# ProPrj_CLOCK_2026-02-21.net
KiCad netlist of a schematic drawn in EasyEDA Pro
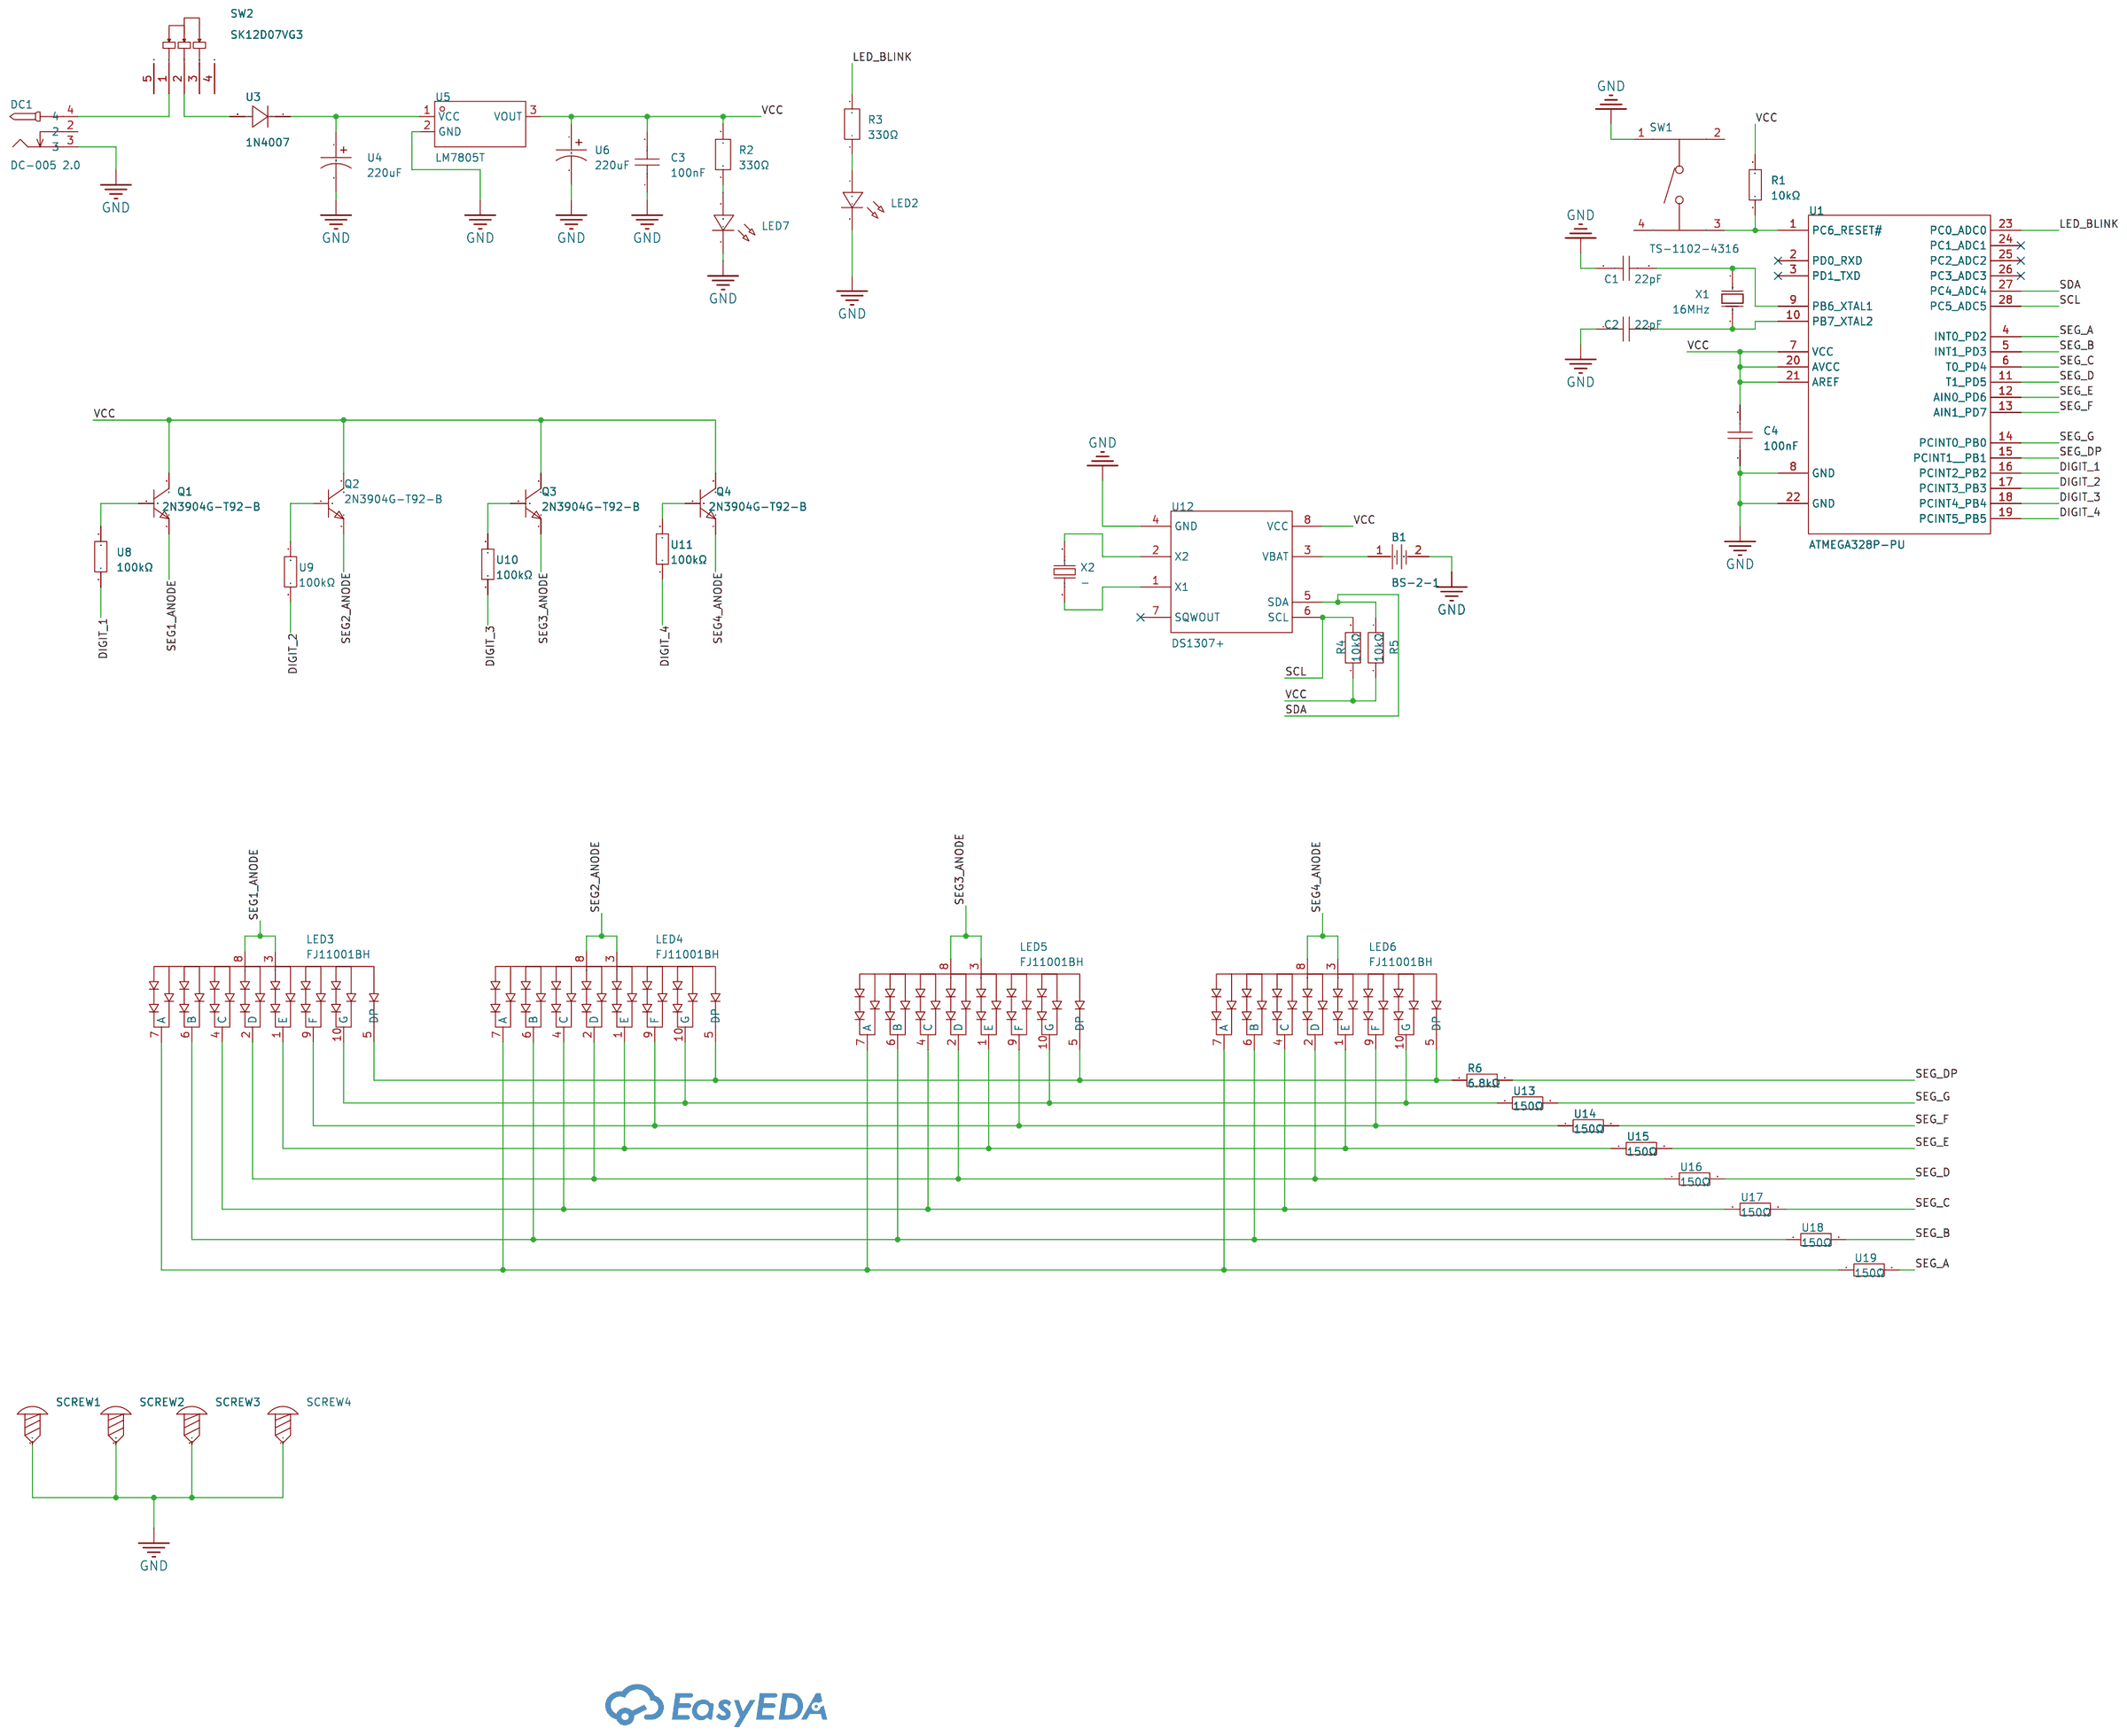
[diagram p0: schematic sheet]

(export (version "E")
  (design (tool "Eeschema 10.0.6"))
  (components
    (comp (ref "B1")
      (value "BS-2-1")
      (footprint "easyedapro:BAT-TH_BS-2-1")
      (fields (field (name "Manufacturer") "QIJEY"))
      (libsource (lib "easyedapro") (part "CR2032-BS-2-1"))
    )
    (comp (ref "C1")
      (value "22pF")
      (footprint "easyedapro:CAP-TH_L5.8-W2.4-P2.54-D0.6")
      (fields
        (field (name "Manufacturer Part") "CC1H220KA1EDCH4B1100")
        (field (name "Manufacturer") "Dersonic(德尔创)")
      )
      (libsource (lib "easyedapro") (part "CC1H220KA1EDCH4B1100"))
    )
    (comp (ref "C2")
      (value "22pF")
      (footprint "easyedapro:CAP-TH_L5.8-W2.4-P2.54-D0.6")
      (fields
        (field (name "Manufacturer Part") "CC1H220KA1EDCH4B1100")
        (field (name "Manufacturer") "Dersonic(德尔创)")
      )
      (libsource (lib "easyedapro") (part "CC1H220KA1EDCH4B1100"))
    )
    (comp (ref "C3")
      (value "100nF")
      (footprint "easyedapro:CAP-TH_L5.0-W2.5-P5.00-D1.0")
      (fields
        (field (name "Manufacturer Part") "CC1H104MC1FD3F6C10MF")
        (field (name "Manufacturer") "Dersonic(德尔创)")
      )
      (libsource (lib "easyedapro") (part "CC1H104MC1FD3F6C10MF"))
    )
    (comp (ref "C4")
      (value "100nF")
      (footprint "easyedapro:CAP-TH_L5.0-W2.5-P5.00-D1.0")
      (fields
        (field (name "Manufacturer Part") "CC1H104MC1FD3F6C10MF")
        (field (name "Manufacturer") "Dersonic(德尔创)")
      )
      (libsource (lib "easyedapro") (part "CC1H104MC1FD3F6C10MF"))
    )
    (comp (ref "DC1")
      (value "DC-005 2.0")
      (footprint "easyedapro:DC-IN-TH_DC-005-5.5-2.0")
      (fields (field (name "Manufacturer") "BOOMELE(博穆精密)"))
      (libsource (lib "easyedapro") (part "DC-005 5.5-2.0MM"))
    )
    (comp (ref "LED2")
      (value "~")
      (footprint "easyedapro:LED-TH_BD3.0-P2.54-FD")
      (libsource (lib "easyedapro") (part "LED_TH-G"))
    )
    (comp (ref "LED3")
      (value "FJ11001BH")
      (footprint "easyedapro:LED-SEG-TH_10P-L34.0-W24.0-P2.54-S30.48-BL")
      (description "Digit/Alpha Size(inch):1 Illumination Color:Red LED Polarity:Common Anode")
      (fields (field (name "Manufacturer") "志浩"))
      (libsource (lib "easyedapro") (part "FJ11001BH"))
    )
    (comp (ref "LED4")
      (value "FJ11001BH")
      (footprint "easyedapro:LED-SEG-TH_10P-L34.0-W24.0-P2.54-S30.48-BL")
      (description "Digit/Alpha Size(inch):1 Illumination Color:Red LED Polarity:Common Anode")
      (fields (field (name "Manufacturer") "志浩"))
      (libsource (lib "easyedapro") (part "FJ11001BH"))
    )
    (comp (ref "LED5")
      (value "FJ11001BH")
      (footprint "easyedapro:LED-SEG-TH_10P-L34.0-W24.0-P2.54-S30.48-BL")
      (description "Digit/Alpha Size(inch):1 Illumination Color:Red LED Polarity:Common Anode")
      (fields (field (name "Manufacturer") "志浩"))
      (libsource (lib "easyedapro") (part "FJ11001BH"))
    )
    (comp (ref "LED6")
      (value "FJ11001BH")
      (footprint "easyedapro:LED-SEG-TH_10P-L34.0-W24.0-P2.54-S30.48-BL")
      (description "Digit/Alpha Size(inch):1 Illumination Color:Red LED Polarity:Common Anode")
      (fields (field (name "Manufacturer") "志浩"))
      (libsource (lib "easyedapro") (part "FJ11001BH"))
    )
    (comp (ref "LED7")
      (value "~")
      (footprint "easyedapro:LED-TH_BD3.0-P2.54-FD")
      (libsource (lib "easyedapro") (part "LED_TH-R"))
    )
    (comp (ref "Q1")
      (value "2N3904G-T92-B")
      (footprint "easyedapro:TO-92-3_L4.9-W3.7-P1.27-L")
      (fields (field (name "Manufacturer") "UTC(友顺)"))
      (libsource (lib "easyedapro") (part "2N3904G-T92-B"))
    )
    (comp (ref "Q2")
      (value "2N3904G-T92-B")
      (footprint "easyedapro:TO-92-3_L4.9-W3.7-P1.27-L")
      (fields (field (name "Manufacturer") "UTC(友顺)"))
      (libsource (lib "easyedapro") (part "2N3904G-T92-B"))
    )
    (comp (ref "Q3")
      (value "2N3904G-T92-B")
      (footprint "easyedapro:TO-92-3_L4.9-W3.7-P1.27-L")
      (fields (field (name "Manufacturer") "UTC(友顺)"))
      (libsource (lib "easyedapro") (part "2N3904G-T92-B"))
    )
    (comp (ref "Q4")
      (value "2N3904G-T92-B")
      (footprint "easyedapro:TO-92-3_L4.9-W3.7-P1.27-L")
      (fields (field (name "Manufacturer") "UTC(友顺)"))
      (libsource (lib "easyedapro") (part "2N3904G-T92-B"))
    )
    (comp (ref "R1")
      (value "10kΩ")
      (footprint "easyedapro:RES-TH_BD1.8-L3.2-P7.20-D0.4")
      (libsource (lib "easyedapro") (part "Res"))
    )
    (comp (ref "R2")
      (value "330Ω")
      (footprint "easyedapro:RES-TH_BD2.7-L6.2-P10.20-D0.4")
      (fields (field (name "Manufacturer Part") "CR1/4W-330Ω±5%-OT52") (field (name "Manufacturer") "VO(翔胜)"))
      (libsource (lib "easyedapro") (part "CR1/4W-330Ω±5%-OT52"))
    )
    (comp (ref "R3")
      (value "330Ω")
      (footprint "easyedapro:RES-TH_BD2.7-L6.2-P10.20-D0.4")
      (fields (field (name "Manufacturer Part") "CR1/4W-330Ω±5%-OT52") (field (name "Manufacturer") "VO(翔胜)"))
      (libsource (lib "easyedapro") (part "CR1/4W-330Ω±5%-OT52"))
    )
    (comp (ref "R4")
      (value "10kΩ")
      (footprint "easyedapro:RES-TH_BD2.7-L6.2-P10.20-D0.4")
      (fields (field (name "Manufacturer Part") "MF1/4W-10K±1%-ST52") (field (name "Manufacturer") "VO(翔胜)"))
      (libsource (lib "easyedapro") (part "MF1/4W-10K±1%-ST52"))
    )
    (comp (ref "R5")
      (value "10kΩ")
      (footprint "easyedapro:RES-TH_BD2.7-L6.2-P10.20-D0.4")
      (fields (field (name "Manufacturer Part") "MF1/4W-10K±1%-ST52") (field (name "Manufacturer") "VO(翔胜)"))
      (libsource (lib "easyedapro") (part "MF1/4W-10K±1%-ST52"))
    )
    (comp (ref "R6")
      (value "6.8kΩ")
      (footprint "easyedapro:RES-TH_BD2.3-L6.5-P10.50-D0.5")
      (fields
        (field (name "Manufacturer Part") "MF1/2WS-6.8KΩ±1% T")
        (field (name "Manufacturer") "CCO(千志电子)")
      )
      (libsource (lib "easyedapro") (part "MF1/2WS-6.8KΩ±1% T52"))
    )
    (comp (ref "SCREW1")
      (value "~")
      (footprint "easyedapro:Screw-Hole-M3")
      (libsource (lib "easyedapro") (part "Screw-Hole"))
    )
    (comp (ref "SCREW2")
      (value "~")
      (footprint "easyedapro:Screw-Hole-M3")
      (libsource (lib "easyedapro") (part "Screw-Hole"))
    )
    (comp (ref "SCREW3")
      (value "~")
      (footprint "easyedapro:Screw-Hole-M3")
      (libsource (lib "easyedapro") (part "Screw-Hole"))
    )
    (comp (ref "SCREW4")
      (value "~")
      (footprint "easyedapro:Screw-Hole-M3")
      (libsource (lib "easyedapro") (part "Screw-Hole"))
    )
    (comp (ref "SW1")
      (value "TS-1102-4316")
      (footprint "easyedapro:KEY-TH_4P-L6.0-W6.0-P4.50-LS6.5")
      (fields (field (name "Manufacturer") "SOFNG(硕方)"))
      (libsource (lib "easyedapro") (part "TS-1102-4316"))
    )
    (comp (ref "SW2")
      (value "SK12D07VG3")
      (footprint "easyedapro:SW-TH_SK12D07VG3")
      (fields (field (name "Manufacturer") "SHOU HAN(首韩)"))
      (libsource (lib "easyedapro") (part "SK12D07VG3_C431547"))
    )
    (comp (ref "U1")
      (value "ATMEGA328P-PU")
      (footprint "easyedapro:DIP-28_L34.6-W7.3-P2.54-LS10.2-BL")
      (fields (field (name "Manufacturer") "MICROCHIP(美国微芯)"))
      (libsource (lib "easyedapro") (part "ATMEGA328P-PU"))
    )
    (comp (ref "U3")
      (value "1N4007")
      (footprint "easyedapro:DO-41_BD2.4-L4.7-P8.70-D0.6-RD")
      (fields (field (name "Manufacturer") "CJ(江苏长电/长晶)"))
      (libsource (lib "easyedapro") (part "1N4007_C5261026"))
    )
    (comp (ref "U4")
      (value "220uF")
      (footprint "easyedapro:CAP-TH_BD6.3-P2.50-D0.6-FD")
      (fields (field (name "Manufacturer Part") "25V220uF CD288") (field (name "Manufacturer") "HRK(鸿瑞凯电子)"))
      (libsource (lib "easyedapro") (part "25V220UF CD288"))
    )
    (comp (ref "U5")
      (value "LM7805T")
      (footprint "easyedapro:TO-220-3_L10.1-W4.7-P2.54-L")
      (fields (field (name "Manufacturer") "HGSEMI(华冠)"))
      (libsource (lib "easyedapro") (part "LM7805T_C7432180"))
    )
    (comp (ref "U6")
      (value "220uF")
      (footprint "easyedapro:CAP-TH_BD6.3-P2.50-D0.6-FD")
      (fields (field (name "Manufacturer Part") "25V220uF CD288") (field (name "Manufacturer") "HRK(鸿瑞凯电子)"))
      (libsource (lib "easyedapro") (part "25V220UF CD288"))
    )
    (comp (ref "U8")
      (value "100kΩ")
      (footprint "easyedapro:RES-TH_BD2.7-L6.2-P10.20-D0.4")
      (fields (field (name "Manufacturer Part") "MF1/4W-100K±1%-OT26") (field (name "Manufacturer") "VO(翔胜)"))
      (libsource (lib "easyedapro") (part "MF1/4W-100K±1%-OT26"))
    )
    (comp (ref "U9")
      (value "100kΩ")
      (footprint "easyedapro:RES-TH_BD2.7-L6.2-P10.20-D0.4")
      (fields (field (name "Manufacturer Part") "MF1/4W-100K±1%-OT26") (field (name "Manufacturer") "VO(翔胜)"))
      (libsource (lib "easyedapro") (part "MF1/4W-100K±1%-OT26"))
    )
    (comp (ref "U10")
      (value "100kΩ")
      (footprint "easyedapro:RES-TH_BD2.7-L6.2-P10.20-D0.4")
      (fields (field (name "Manufacturer Part") "MF1/4W-100K±1%-OT26") (field (name "Manufacturer") "VO(翔胜)"))
      (libsource (lib "easyedapro") (part "MF1/4W-100K±1%-OT26"))
    )
    (comp (ref "U11")
      (value "100kΩ")
      (footprint "easyedapro:RES-TH_BD2.7-L6.2-P10.20-D0.4")
      (fields (field (name "Manufacturer Part") "MF1/4W-100K±1%-OT26") (field (name "Manufacturer") "VO(翔胜)"))
      (libsource (lib "easyedapro") (part "MF1/4W-100K±1%-OT26"))
    )
    (comp (ref "U12")
      (value "DS1307+")
      (footprint "easyedapro:DIP-8_L9.8-W6.6-P2.54-LS7.6-BL")
      (fields (field (name "Manufacturer") "ADI(亚德诺)/MAXIM(美信)"))
      (libsource (lib "easyedapro") (part "DS1307+"))
    )
    (comp (ref "U13")
      (value "150Ω")
      (footprint "easyedapro:RES-TH_BD2.7-L6.2-P10.20-D0.4")
      (fields (field (name "Manufacturer Part") "KNP1WS-150Ω±5%-XT52") (field (name "Manufacturer") "VO(翔胜)"))
      (libsource (lib "easyedapro") (part "KNP1WS-150Ω±5%-XT52"))
    )
    (comp (ref "U14")
      (value "150Ω")
      (footprint "easyedapro:RES-TH_BD2.7-L6.2-P10.20-D0.4")
      (fields (field (name "Manufacturer Part") "KNP1WS-150Ω±5%-XT52") (field (name "Manufacturer") "VO(翔胜)"))
      (libsource (lib "easyedapro") (part "KNP1WS-150Ω±5%-XT52"))
    )
    (comp (ref "U15")
      (value "150Ω")
      (footprint "easyedapro:RES-TH_BD2.7-L6.2-P10.20-D0.4")
      (fields (field (name "Manufacturer Part") "KNP1WS-150Ω±5%-XT52") (field (name "Manufacturer") "VO(翔胜)"))
      (libsource (lib "easyedapro") (part "KNP1WS-150Ω±5%-XT52"))
    )
    (comp (ref "U16")
      (value "150Ω")
      (footprint "easyedapro:RES-TH_BD2.7-L6.2-P10.20-D0.4")
      (fields (field (name "Manufacturer Part") "KNP1WS-150Ω±5%-XT52") (field (name "Manufacturer") "VO(翔胜)"))
      (libsource (lib "easyedapro") (part "KNP1WS-150Ω±5%-XT52"))
    )
    (comp (ref "U17")
      (value "150Ω")
      (footprint "easyedapro:RES-TH_BD2.7-L6.2-P10.20-D0.4")
      (fields (field (name "Manufacturer Part") "KNP1WS-150Ω±5%-XT52") (field (name "Manufacturer") "VO(翔胜)"))
      (libsource (lib "easyedapro") (part "KNP1WS-150Ω±5%-XT52"))
    )
    (comp (ref "U18")
      (value "150Ω")
      (footprint "easyedapro:RES-TH_BD2.7-L6.2-P10.20-D0.4")
      (fields (field (name "Manufacturer Part") "KNP1WS-150Ω±5%-XT52") (field (name "Manufacturer") "VO(翔胜)"))
      (libsource (lib "easyedapro") (part "KNP1WS-150Ω±5%-XT52"))
    )
    (comp (ref "U19")
      (value "150Ω")
      (footprint "easyedapro:RES-TH_BD2.7-L6.2-P10.20-D0.4")
      (fields (field (name "Manufacturer Part") "KNP1WS-150Ω±5%-XT52") (field (name "Manufacturer") "VO(翔胜)"))
      (libsource (lib "easyedapro") (part "KNP1WS-150Ω±5%-XT52"))
    )
    (comp (ref "X1")
      (value "16MHz")
      (footprint "easyedapro:OSC-TH_L10.0-W4.5-P5.00")
      (fields (field (name "Manufacturer Part") "X49SD16MSD2SC") (field (name "Manufacturer") "YXC(扬兴晶振)"))
      (libsource (lib "easyedapro") (part "X49SD16MSD2SC"))
    )
    (comp (ref "X2")
      (value "-")
      (footprint "easyedapro:OSC-TH_BD3.0-P1.10-D0.4")
      (description "Type:- Frequency:- Load Capacitance:- Operating Temperature:- Operating Temperature:-")
      (fields (field (name "Manufacturer Part") "DT-38 32.768KHz") (field (name "Manufacturer") "KDS(大真空)"))
      (libsource (lib "easyedapro") (part "DT-38 32.768KHz"))
    )
  )
  (nets
    (net (code "1") (name "/DIGIT_1") (class "Default")
      (node (ref "U1") (pin "16") (pinfunction "PCINT2_PB2_16") (pintype "bidirectional"))
      (node (ref "U8") (pin "1") (pinfunction "1_1") (pintype "unspecified"))
    )
    (net (code "2") (name "/DIGIT_2") (class "Default")
      (node (ref "U1") (pin "17") (pinfunction "PCINT3_PB3_17") (pintype "bidirectional"))
      (node (ref "U9") (pin "1") (pinfunction "1_1") (pintype "unspecified"))
    )
    (net (code "3") (name "/DIGIT_3") (class "Default")
      (node (ref "U1") (pin "18") (pinfunction "PCINT4_PB4_18") (pintype "bidirectional"))
      (node (ref "U10") (pin "1") (pinfunction "1_1") (pintype "unspecified"))
    )
    (net (code "4") (name "/DIGIT_4") (class "Default")
      (node (ref "U1") (pin "19") (pinfunction "PCINT5_PB5_19") (pintype "bidirectional"))
      (node (ref "U11") (pin "1") (pinfunction "1_1") (pintype "unspecified"))
    )
    (net (code "5") (name "/LED_BLINK") (class "Default")
      (node (ref "R3") (pin "2") (pinfunction "2_2") (pintype "unspecified"))
      (node (ref "U1") (pin "23") (pinfunction "PC0_ADC0_23") (pintype "bidirectional"))
    )
    (net (code "6") (name "/SCL") (class "Default")
      (node (ref "R4") (pin "2") (pinfunction "2_2") (pintype "unspecified"))
      (node (ref "U1") (pin "28") (pinfunction "PC5_ADC5_28") (pintype "bidirectional"))
      (node (ref "U12") (pin "6") (pinfunction "SCL_6") (pintype "unspecified"))
    )
    (net (code "7") (name "/SDA") (class "Default")
      (node (ref "R5") (pin "1") (pinfunction "1_1") (pintype "unspecified"))
      (node (ref "U1") (pin "27") (pinfunction "PC4_ADC4_27") (pintype "bidirectional"))
      (node (ref "U12") (pin "5") (pinfunction "SDA_5") (pintype "bidirectional"))
    )
    (net (code "8") (name "/SEG1_ANODE") (class "Default")
      (node (ref "LED3") (pin "3") (pinfunction "3_3") (pintype "input"))
      (node (ref "LED3") (pin "8") (pinfunction "11_8") (pintype "input"))
      (node (ref "Q1") (pin "1") (pinfunction "E_1") (pintype "unspecified"))
    )
    (net (code "9") (name "/SEG2_ANODE") (class "Default")
      (node (ref "LED4") (pin "3") (pinfunction "3_3") (pintype "input"))
      (node (ref "LED4") (pin "8") (pinfunction "11_8") (pintype "input"))
      (node (ref "Q2") (pin "1") (pinfunction "E_1") (pintype "unspecified"))
    )
    (net (code "10") (name "/SEG3_ANODE") (class "Default")
      (node (ref "LED5") (pin "3") (pinfunction "3_3") (pintype "input"))
      (node (ref "LED5") (pin "8") (pinfunction "11_8") (pintype "input"))
      (node (ref "Q3") (pin "1") (pinfunction "E_1") (pintype "unspecified"))
    )
    (net (code "11") (name "/SEG4_ANODE") (class "Default")
      (node (ref "LED6") (pin "3") (pinfunction "3_3") (pintype "input"))
      (node (ref "LED6") (pin "8") (pinfunction "11_8") (pintype "input"))
      (node (ref "Q4") (pin "1") (pinfunction "E_1") (pintype "unspecified"))
    )
    (net (code "12") (name "/SEG_A") (class "Default")
      (node (ref "U1") (pin "4") (pinfunction "INT0_PD2_4") (pintype "bidirectional"))
      (node (ref "U19") (pin "2") (pinfunction "2_2") (pintype "unspecified"))
    )
    (net (code "13") (name "/SEG_B") (class "Default")
      (node (ref "U1") (pin "5") (pinfunction "INT1_PD3_5") (pintype "bidirectional"))
      (node (ref "U18") (pin "2") (pinfunction "2_2") (pintype "unspecified"))
    )
    (net (code "14") (name "/SEG_C") (class "Default")
      (node (ref "U1") (pin "6") (pinfunction "T0_PD4_6") (pintype "bidirectional"))
      (node (ref "U17") (pin "2") (pinfunction "2_2") (pintype "unspecified"))
    )
    (net (code "15") (name "/SEG_D") (class "Default")
      (node (ref "U1") (pin "11") (pinfunction "T1_PD5_11") (pintype "bidirectional"))
      (node (ref "U16") (pin "2") (pinfunction "2_2") (pintype "unspecified"))
    )
    (net (code "16") (name "/SEG_DP") (class "Default")
      (node (ref "R6") (pin "2") (pinfunction "2_2") (pintype "unspecified"))
      (node (ref "U1") (pin "15") (pinfunction "PCINT1__PB1_15") (pintype "bidirectional"))
    )
    (net (code "17") (name "/SEG_E") (class "Default")
      (node (ref "U1") (pin "12") (pinfunction "AIN0_PD6_12") (pintype "bidirectional"))
      (node (ref "U15") (pin "2") (pinfunction "2_2") (pintype "unspecified"))
    )
    (net (code "18") (name "/SEG_F") (class "Default")
      (node (ref "U1") (pin "13") (pinfunction "AIN1_PD7_13") (pintype "bidirectional"))
      (node (ref "U14") (pin "2") (pinfunction "2_2") (pintype "unspecified"))
    )
    (net (code "19") (name "/SEG_G") (class "Default")
      (node (ref "U1") (pin "14") (pinfunction "PCINT0_PB0_14") (pintype "bidirectional"))
      (node (ref "U13") (pin "2") (pinfunction "2_2") (pintype "unspecified"))
    )
    (net (code "20") (name "/VCC") (class "Default")
      (node (ref "C3") (pin "2") (pinfunction "2_2") (pintype "unspecified"))
      (node (ref "C4") (pin "2") (pinfunction "2_2") (pintype "unspecified"))
      (node (ref "Q1") (pin "3") (pinfunction "C_3") (pintype "unspecified"))
      (node (ref "Q2") (pin "3") (pinfunction "C_3") (pintype "unspecified"))
      (node (ref "Q3") (pin "3") (pinfunction "C_3") (pintype "unspecified"))
      (node (ref "Q4") (pin "3") (pinfunction "C_3") (pintype "unspecified"))
      (node (ref "R1") (pin "2") (pinfunction "2_2") (pintype "input"))
      (node (ref "R2") (pin "2") (pinfunction "2_2") (pintype "unspecified"))
      (node (ref "R4") (pin "1") (pinfunction "1_1") (pintype "unspecified"))
      (node (ref "R5") (pin "2") (pinfunction "2_2") (pintype "unspecified"))
      (node (ref "U1") (pin "20") (pinfunction "AVCC_20") (pintype "unspecified"))
      (node (ref "U1") (pin "21") (pinfunction "AREF_21") (pintype "unspecified"))
      (node (ref "U1") (pin "7") (pinfunction "VCC_7") (pintype "unspecified"))
      (node (ref "U12") (pin "8") (pinfunction "VCC_8") (pintype "unspecified"))
      (node (ref "U5") (pin "3") (pinfunction "VOUT_3") (pintype "unspecified"))
      (node (ref "U6") (pin "1") (pinfunction "1_1") (pintype "unspecified"))
    )
    (net (code "21") (name "GND") (class "Default")
      (node (ref "B1") (pin "2") (pinfunction "2_2") (pintype "input"))
      (node (ref "C1") (pin "1") (pinfunction "1_1") (pintype "unspecified"))
      (node (ref "C2") (pin "1") (pinfunction "1_1") (pintype "unspecified"))
      (node (ref "C3") (pin "1") (pinfunction "1_1") (pintype "unspecified"))
      (node (ref "C4") (pin "1") (pinfunction "1_1") (pintype "unspecified"))
      (node (ref "DC1") (pin "3") (pinfunction "3_3") (pintype "unspecified"))
      (node (ref "LED2") (pin "2") (pinfunction "A_2") (pintype "input"))
      (node (ref "LED7") (pin "2") (pinfunction "A_2") (pintype "input"))
      (node (ref "SCREW1") (pin "1") (pinfunction "1_1") (pintype "input"))
      (node (ref "SCREW2") (pin "1") (pinfunction "1_1") (pintype "input"))
      (node (ref "SCREW3") (pin "1") (pinfunction "1_1") (pintype "input"))
      (node (ref "SCREW4") (pin "1") (pinfunction "1_1") (pintype "input"))
      (node (ref "SW1") (pin "1") (pinfunction "1_1") (pintype "unspecified"))
      (node (ref "U1") (pin "22") (pinfunction "GND_22") (pintype "unspecified"))
      (node (ref "U1") (pin "8") (pinfunction "GND_8") (pintype "unspecified"))
      (node (ref "U12") (pin "4") (pinfunction "GND_4") (pintype "unspecified"))
      (node (ref "U4") (pin "2") (pinfunction "2_2") (pintype "unspecified"))
      (node (ref "U5") (pin "2") (pinfunction "GND_2") (pintype "unspecified"))
      (node (ref "U6") (pin "2") (pinfunction "2_2") (pintype "unspecified"))
    )
    (net (code "22") (name "Net-(DC1-Pad4)") (class "Default")
      (node (ref "DC1") (pin "4") (pinfunction "4_4") (pintype "unspecified"))
      (node (ref "SW2") (pin "1") (pinfunction "1_1") (pintype "unspecified"))
    )
    (net (code "23") (name "Net-(LED2-C)") (class "Default")
      (node (ref "LED2") (pin "1") (pinfunction "C_1") (pintype "input"))
      (node (ref "R3") (pin "1") (pinfunction "1_1") (pintype "unspecified"))
    )
    (net (code "24") (name "Net-(LED3-A)") (class "Default")
      (node (ref "LED3") (pin "7") (pinfunction "A_7") (pintype "input"))
      (node (ref "LED4") (pin "7") (pinfunction "A_7") (pintype "input"))
      (node (ref "LED5") (pin "7") (pinfunction "A_7") (pintype "input"))
      (node (ref "LED6") (pin "7") (pinfunction "A_7") (pintype "input"))
      (node (ref "U19") (pin "1") (pinfunction "1_1") (pintype "unspecified"))
    )
    (net (code "25") (name "Net-(LED3-B)") (class "Default")
      (node (ref "LED3") (pin "6") (pinfunction "B_6") (pintype "input"))
      (node (ref "LED4") (pin "6") (pinfunction "B_6") (pintype "input"))
      (node (ref "LED5") (pin "6") (pinfunction "B_6") (pintype "input"))
      (node (ref "LED6") (pin "6") (pinfunction "B_6") (pintype "input"))
      (node (ref "U18") (pin "1") (pinfunction "1_1") (pintype "unspecified"))
    )
    (net (code "26") (name "Net-(LED3-C)") (class "Default")
      (node (ref "LED3") (pin "4") (pinfunction "C_4") (pintype "input"))
      (node (ref "LED4") (pin "4") (pinfunction "C_4") (pintype "input"))
      (node (ref "LED5") (pin "4") (pinfunction "C_4") (pintype "input"))
      (node (ref "LED6") (pin "4") (pinfunction "C_4") (pintype "input"))
      (node (ref "U17") (pin "1") (pinfunction "1_1") (pintype "unspecified"))
    )
    (net (code "27") (name "Net-(LED3-D)") (class "Default")
      (node (ref "LED3") (pin "2") (pinfunction "D_2") (pintype "input"))
      (node (ref "LED4") (pin "2") (pinfunction "D_2") (pintype "input"))
      (node (ref "LED5") (pin "2") (pinfunction "D_2") (pintype "input"))
      (node (ref "LED6") (pin "2") (pinfunction "D_2") (pintype "input"))
      (node (ref "U16") (pin "1") (pinfunction "1_1") (pintype "unspecified"))
    )
    (net (code "28") (name "Net-(LED3-DP)") (class "Default")
      (node (ref "LED3") (pin "5") (pinfunction "DP_5") (pintype "input"))
      (node (ref "LED4") (pin "5") (pinfunction "DP_5") (pintype "input"))
      (node (ref "LED5") (pin "5") (pinfunction "DP_5") (pintype "input"))
      (node (ref "LED6") (pin "5") (pinfunction "DP_5") (pintype "input"))
      (node (ref "R6") (pin "1") (pinfunction "1_1") (pintype "unspecified"))
    )
    (net (code "29") (name "Net-(LED3-E)") (class "Default")
      (node (ref "LED3") (pin "1") (pinfunction "E_1") (pintype "input"))
      (node (ref "LED4") (pin "1") (pinfunction "E_1") (pintype "input"))
      (node (ref "LED5") (pin "1") (pinfunction "E_1") (pintype "input"))
      (node (ref "LED6") (pin "1") (pinfunction "E_1") (pintype "input"))
      (node (ref "U15") (pin "1") (pinfunction "1_1") (pintype "unspecified"))
    )
    (net (code "30") (name "Net-(LED3-F)") (class "Default")
      (node (ref "LED3") (pin "9") (pinfunction "F_9") (pintype "input"))
      (node (ref "LED4") (pin "9") (pinfunction "F_9") (pintype "input"))
      (node (ref "LED5") (pin "9") (pinfunction "F_9") (pintype "input"))
      (node (ref "LED6") (pin "9") (pinfunction "F_9") (pintype "input"))
      (node (ref "U14") (pin "1") (pinfunction "1_1") (pintype "unspecified"))
    )
    (net (code "31") (name "Net-(LED3-G)") (class "Default")
      (node (ref "LED3") (pin "10") (pinfunction "G_10") (pintype "input"))
      (node (ref "LED4") (pin "10") (pinfunction "G_10") (pintype "input"))
      (node (ref "LED5") (pin "10") (pinfunction "G_10") (pintype "input"))
      (node (ref "LED6") (pin "10") (pinfunction "G_10") (pintype "input"))
      (node (ref "U13") (pin "1") (pinfunction "1_1") (pintype "unspecified"))
    )
    (net (code "32") (name "Net-(LED7-C)") (class "Default")
      (node (ref "LED7") (pin "1") (pinfunction "C_1") (pintype "input"))
      (node (ref "R2") (pin "1") (pinfunction "1_1") (pintype "unspecified"))
    )
    (net (code "33") (name "Net-(Q1-B)") (class "Default")
      (node (ref "Q1") (pin "2") (pinfunction "B_2") (pintype "unspecified"))
      (node (ref "U8") (pin "2") (pinfunction "2_2") (pintype "unspecified"))
    )
    (net (code "34") (name "Net-(Q2-B)") (class "Default")
      (node (ref "Q2") (pin "2") (pinfunction "B_2") (pintype "unspecified"))
      (node (ref "U9") (pin "2") (pinfunction "2_2") (pintype "unspecified"))
    )
    (net (code "35") (name "Net-(Q3-B)") (class "Default")
      (node (ref "Q3") (pin "2") (pinfunction "B_2") (pintype "unspecified"))
      (node (ref "U10") (pin "2") (pinfunction "2_2") (pintype "unspecified"))
    )
    (net (code "36") (name "Net-(Q4-B)") (class "Default")
      (node (ref "Q4") (pin "2") (pinfunction "B_2") (pintype "unspecified"))
      (node (ref "U11") (pin "2") (pinfunction "2_2") (pintype "unspecified"))
    )
    (net (code "37") (name "Net-(U1-PB6_XTAL1)") (class "Default")
      (node (ref "C1") (pin "2") (pinfunction "2_2") (pintype "unspecified"))
      (node (ref "U1") (pin "9") (pinfunction "PB6_XTAL1_9") (pintype "bidirectional"))
      (node (ref "X1") (pin "1") (pinfunction "OSC1_1") (pintype "input"))
    )
    (net (code "38") (name "Net-(U1-PB7_XTAL2)") (class "Default")
      (node (ref "C2") (pin "2") (pinfunction "2_2") (pintype "unspecified"))
      (node (ref "U1") (pin "10") (pinfunction "PB7_XTAL2_10") (pintype "bidirectional"))
      (node (ref "X1") (pin "2") (pinfunction "OSC2_2") (pintype "input"))
    )
    (net (code "39") (name "Net-(U1-PC6_RESET#)") (class "Default")
      (node (ref "R1") (pin "1") (pinfunction "1_1") (pintype "input"))
      (node (ref "SW1") (pin "3") (pinfunction "3_3") (pintype "unspecified"))
      (node (ref "U1") (pin "1") (pinfunction "PC6_RESET#_1") (pintype "bidirectional"))
    )
    (net (code "40") (name "Net-(U3-A)") (class "Default")
      (node (ref "SW2") (pin "2") (pinfunction "2_2") (pintype "unspecified"))
      (node (ref "U3") (pin "2") (pinfunction "A_2") (pintype "unspecified"))
    )
    (net (code "41") (name "Net-(U3-C)") (class "Default")
      (node (ref "U3") (pin "1") (pinfunction "C_1") (pintype "unspecified"))
      (node (ref "U4") (pin "1") (pinfunction "1_1") (pintype "unspecified"))
      (node (ref "U5") (pin "1") (pinfunction "VCC_1") (pintype "unspecified"))
    )
    (net (code "42") (name "Net-(U12-VBAT)") (class "Default")
      (node (ref "B1") (pin "1") (pinfunction "1_1") (pintype "input"))
      (node (ref "U12") (pin "3") (pinfunction "VBAT_3") (pintype "unspecified"))
    )
    (net (code "43") (name "Net-(U12-X1)") (class "Default")
      (node (ref "U12") (pin "1") (pinfunction "X1_1") (pintype "unspecified"))
      (node (ref "X2") (pin "1") (pinfunction "1_1") (pintype "unspecified"))
    )
    (net (code "44") (name "Net-(U12-X2)") (class "Default")
      (node (ref "U12") (pin "2") (pinfunction "X2_2") (pintype "unspecified"))
      (node (ref "X2") (pin "2") (pinfunction "2_2") (pintype "unspecified"))
    )
    (net (code "45") (name "unconnected-(DC1-Pad2)") (class "Default")
      (node (ref "DC1") (pin "2") (pinfunction "2_2") (pintype "unspecified"))
    )
    (net (code "46") (name "unconnected-(SW1-Pad2)") (class "Default")
      (node (ref "SW1") (pin "2") (pinfunction "2_2") (pintype "unspecified"))
    )
    (net (code "47") (name "unconnected-(SW1-Pad4)") (class "Default")
      (node (ref "SW1") (pin "4") (pinfunction "4_4") (pintype "unspecified"))
    )
    (net (code "48") (name "unconnected-(SW2-Pad3)") (class "Default")
      (node (ref "SW2") (pin "3") (pinfunction "3_3") (pintype "unspecified"))
    )
    (net (code "49") (name "unconnected-(SW2-Pad4)") (class "Default")
      (node (ref "SW2") (pin "4") (pinfunction "4_4") (pintype "unspecified"))
    )
    (net (code "50") (name "unconnected-(SW2-Pad5)") (class "Default")
      (node (ref "SW2") (pin "5") (pinfunction "5_5") (pintype "unspecified"))
    )
    (net (code "51") (name "unconnected-(U1-PC1_ADC1-Pad24)") (class "Default")
      (node (ref "U1") (pin "24") (pinfunction "PC1_ADC1_24") (pintype "bidirectional+no_connect"))
    )
    (net (code "52") (name "unconnected-(U1-PC2_ADC2-Pad25)") (class "Default")
      (node (ref "U1") (pin "25") (pinfunction "PC2_ADC2_25") (pintype "bidirectional+no_connect"))
    )
    (net (code "53") (name "unconnected-(U1-PC3_ADC3-Pad26)") (class "Default")
      (node (ref "U1") (pin "26") (pinfunction "PC3_ADC3_26") (pintype "bidirectional+no_connect"))
    )
    (net (code "54") (name "unconnected-(U1-PD0_RXD-Pad2)") (class "Default")
      (node (ref "U1") (pin "2") (pinfunction "PD0_RXD_2") (pintype "bidirectional+no_connect"))
    )
    (net (code "55") (name "unconnected-(U1-PD1_TXD-Pad3)") (class "Default")
      (node (ref "U1") (pin "3") (pinfunction "PD1_TXD_3") (pintype "bidirectional+no_connect"))
    )
    (net (code "56") (name "unconnected-(U12-SQWOUT-Pad7)") (class "Default")
      (node (ref "U12") (pin "7") (pinfunction "SQWOUT_7") (pintype "unspecified+no_connect"))
    )
  )
)
